# amplifier-special.net
KiCad netlist of a schematic drawn in Altium Designer
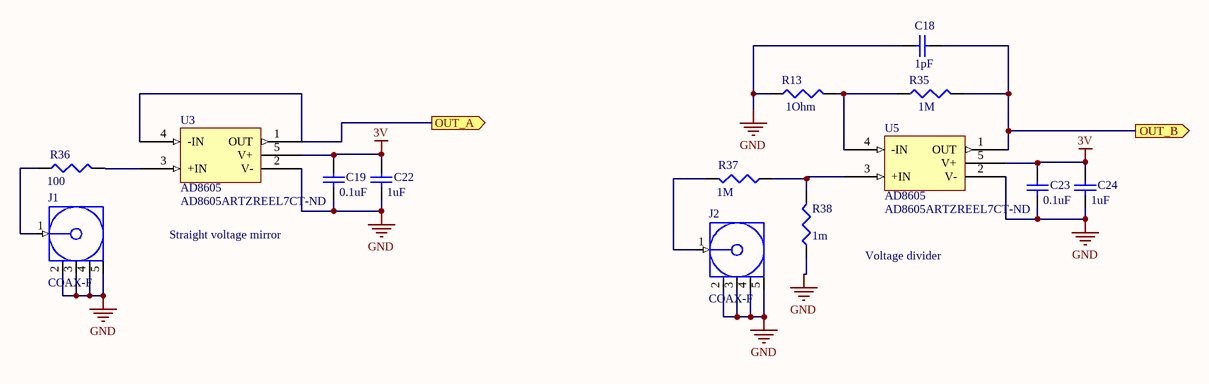
[diagram p0: amplifier-special.SchDoc]

(export (version "E")
  (design (tool "Eeschema 10.0.6"))
  (components
    (comp (ref "C18")
      (value "1pF")
      (footprint "0402")
      (description "Capacitor (Semiconductor SIM Model)")
      (fields (field (name "Comment") "0.1uF") (field (name "PUBLISHER") "Altium Limited"))
      (libsource (lib "Miscellaneous Devices") (part "Cap Semi"))
    )
    (comp (ref "C19")
      (value "0.1uF")
      (footprint "0402")
      (description "Capacitor (Semiconductor SIM Model)")
      (fields (field (name "PUBLISHER") "Altium Limited"))
      (libsource (lib "Miscellaneous Devices") (part "Cap Semi"))
    )
    (comp (ref "C22")
      (value "1uF")
      (footprint "1608[0603]")
      (description "Capacitor (Semiconductor SIM Model)")
      (fields (field (name "PUBLISHER") "Altium Limited"))
      (libsource (lib "Miscellaneous Devices") (part "Cap Semi"))
    )
    (comp (ref "C23")
      (value "0.1uF")
      (footprint "0402")
      (description "Capacitor (Semiconductor SIM Model)")
      (fields (field (name "PUBLISHER") "Altium Limited"))
      (libsource (lib "Miscellaneous Devices") (part "Cap Semi"))
    )
    (comp (ref "C24")
      (value "1uF")
      (footprint "1608[0603]")
      (description "Capacitor (Semiconductor SIM Model)")
      (fields (field (name "PUBLISHER") "Altium Limited"))
      (libsource (lib "Miscellaneous Devices") (part "Cap Semi"))
    )
    (comp (ref "J1")
      (value "COAX-F")
      (footprint "MCX5.08-H5")
      (fields (field (name "PUBLISHER") "Altium Limited"))
      (libsource (lib "Miscellaneous Connectors") (part "COAX-F"))
    )
    (comp (ref "J2")
      (value "COAX-F")
      (footprint "MCX5.08-H5")
      (fields (field (name "PUBLISHER") "Altium Limited"))
      (libsource (lib "Miscellaneous Connectors") (part "COAX-F"))
    )
    (comp (ref "R13")
      (value "1Ohm")
      (footprint "J1-0603")
      (description "Resistor")
      (fields (field (name "Comment") "1 Ohm") (field (name "PUBLISHER") "Altium Limited"))
      (libsource (lib "Miscellaneous Devices") (part "Res3"))
    )
    (comp (ref "R35")
      (value "1M")
      (footprint "0402")
      (description "Resistor")
      (fields (field (name "PUBLISHER") "Altium Limited"))
      (libsource (lib "Miscellaneous Devices") (part "Res3"))
    )
    (comp (ref "R36")
      (value "100")
      (footprint "0402")
      (description "Resistor")
      (fields (field (name "PUBLISHER") "Altium Limited"))
      (libsource (lib "Miscellaneous Devices") (part "Res3"))
    )
    (comp (ref "R37")
      (value "1M")
      (footprint "0402")
      (description "Resistor")
      (fields (field (name "PUBLISHER") "Altium Limited"))
      (libsource (lib "Miscellaneous Devices") (part "Res3"))
    )
    (comp (ref "R38")
      (value "1m")
      (footprint "14-1210")
      (description "Resistor")
      (fields (field (name "PUBLISHER") "Altium Limited"))
      (libsource (lib "Miscellaneous Devices") (part "Res3"))
    )
    (comp (ref "U3")
      (value "AD8605")
      (footprint "SOP-65P200X125-5N")
      (description "Low noise, precision rail-to-rail op-amp.")
      (fields (field (name "SUPPLIER PART NUMBER 1") "AD8605ARTZREEL7CT-ND"))
      (libsource (lib "PAY") (part "AD8605"))
    )
    (comp (ref "U5")
      (value "AD8605")
      (footprint "SOP-65P200X125-5N")
      (description "Low noise, precision rail-to-rail op-amp.")
      (fields (field (name "SUPPLIER PART NUMBER 1") "AD8605ARTZREEL7CT-ND"))
      (libsource (lib "PAY") (part "AD8605"))
    )
  )
  (nets
    (net (code "1") (name "/OUT_A") (class "Default")
      (node (ref "U3") (pin "1") (pinfunction "OUT_1") (pintype "output"))
      (node (ref "U3") (pin "4") (pinfunction "-IN_4") (pintype "input"))
    )
    (net (code "2") (name "/OUT_B") (class "Default")
      (node (ref "C18") (pin "1") (pinfunction "1_1") (pintype "passive"))
      (node (ref "R35") (pin "2") (pinfunction "2_2") (pintype "passive"))
      (node (ref "U5") (pin "1") (pinfunction "OUT_1") (pintype "output"))
    )
    (net (code "3") (name "3V") (class "Default")
      (node (ref "C19") (pin "2") (pinfunction "2_2") (pintype "passive"))
      (node (ref "C22") (pin "2") (pinfunction "2_2") (pintype "passive"))
      (node (ref "C23") (pin "2") (pinfunction "2_2") (pintype "passive"))
      (node (ref "C24") (pin "2") (pinfunction "2_2") (pintype "passive"))
      (node (ref "U3") (pin "5") (pinfunction "V+_5") (pintype "power_in"))
      (node (ref "U5") (pin "5") (pinfunction "V+_5") (pintype "power_in"))
    )
    (net (code "4") (name "GND") (class "Default")
      (node (ref "C18") (pin "2") (pinfunction "2_2") (pintype "passive"))
      (node (ref "C19") (pin "1") (pinfunction "1_1") (pintype "passive"))
      (node (ref "C22") (pin "1") (pinfunction "1_1") (pintype "passive"))
      (node (ref "C23") (pin "1") (pinfunction "1_1") (pintype "passive"))
      (node (ref "C24") (pin "1") (pinfunction "1_1") (pintype "passive"))
      (node (ref "J1") (pin "2") (pinfunction "GND_2") (pintype "power_in"))
      (node (ref "J1") (pin "3") (pinfunction "GND_3") (pintype "power_in"))
      (node (ref "J1") (pin "4") (pinfunction "GND_4") (pintype "power_in"))
      (node (ref "J1") (pin "5") (pinfunction "GND_5") (pintype "power_in"))
      (node (ref "J2") (pin "2") (pinfunction "GND_2") (pintype "power_in"))
      (node (ref "J2") (pin "3") (pinfunction "GND_3") (pintype "power_in"))
      (node (ref "J2") (pin "4") (pinfunction "GND_4") (pintype "power_in"))
      (node (ref "J2") (pin "5") (pinfunction "GND_5") (pintype "power_in"))
      (node (ref "R13") (pin "1") (pinfunction "1_1") (pintype "passive"))
      (node (ref "R38") (pin "1") (pinfunction "1_1") (pintype "passive"))
      (node (ref "U3") (pin "2") (pinfunction "V-_2") (pintype "power_in"))
      (node (ref "U5") (pin "2") (pinfunction "V-_2") (pintype "power_in"))
    )
    (net (code "5") (name "Net-(J1-Signal)") (class "Default")
      (node (ref "J1") (pin "1") (pinfunction "Signal_1") (pintype "input"))
      (node (ref "R36") (pin "1") (pinfunction "1_1") (pintype "passive"))
    )
    (net (code "6") (name "Net-(J2-Signal)") (class "Default")
      (node (ref "J2") (pin "1") (pinfunction "Signal_1") (pintype "input"))
      (node (ref "R37") (pin "2") (pinfunction "2_2") (pintype "passive"))
    )
    (net (code "7") (name "Net-(U3-+IN)") (class "Default")
      (node (ref "R36") (pin "2") (pinfunction "2_2") (pintype "passive"))
      (node (ref "U3") (pin "3") (pinfunction "+IN_3") (pintype "input"))
    )
    (net (code "8") (name "Net-(U5-+IN)") (class "Default")
      (node (ref "R37") (pin "1") (pinfunction "1_1") (pintype "passive"))
      (node (ref "R38") (pin "2") (pinfunction "2_2") (pintype "passive"))
      (node (ref "U5") (pin "3") (pinfunction "+IN_3") (pintype "input"))
    )
    (net (code "9") (name "Net-(U5--IN)") (class "Default")
      (node (ref "R13") (pin "2") (pinfunction "2_2") (pintype "passive"))
      (node (ref "R35") (pin "1") (pinfunction "1_1") (pintype "passive"))
      (node (ref "U5") (pin "4") (pinfunction "-IN_4") (pintype "input"))
    )
  )
)
